# zulu_a7_6.net
KiCad netlist of a schematic drawn in Altium Designer
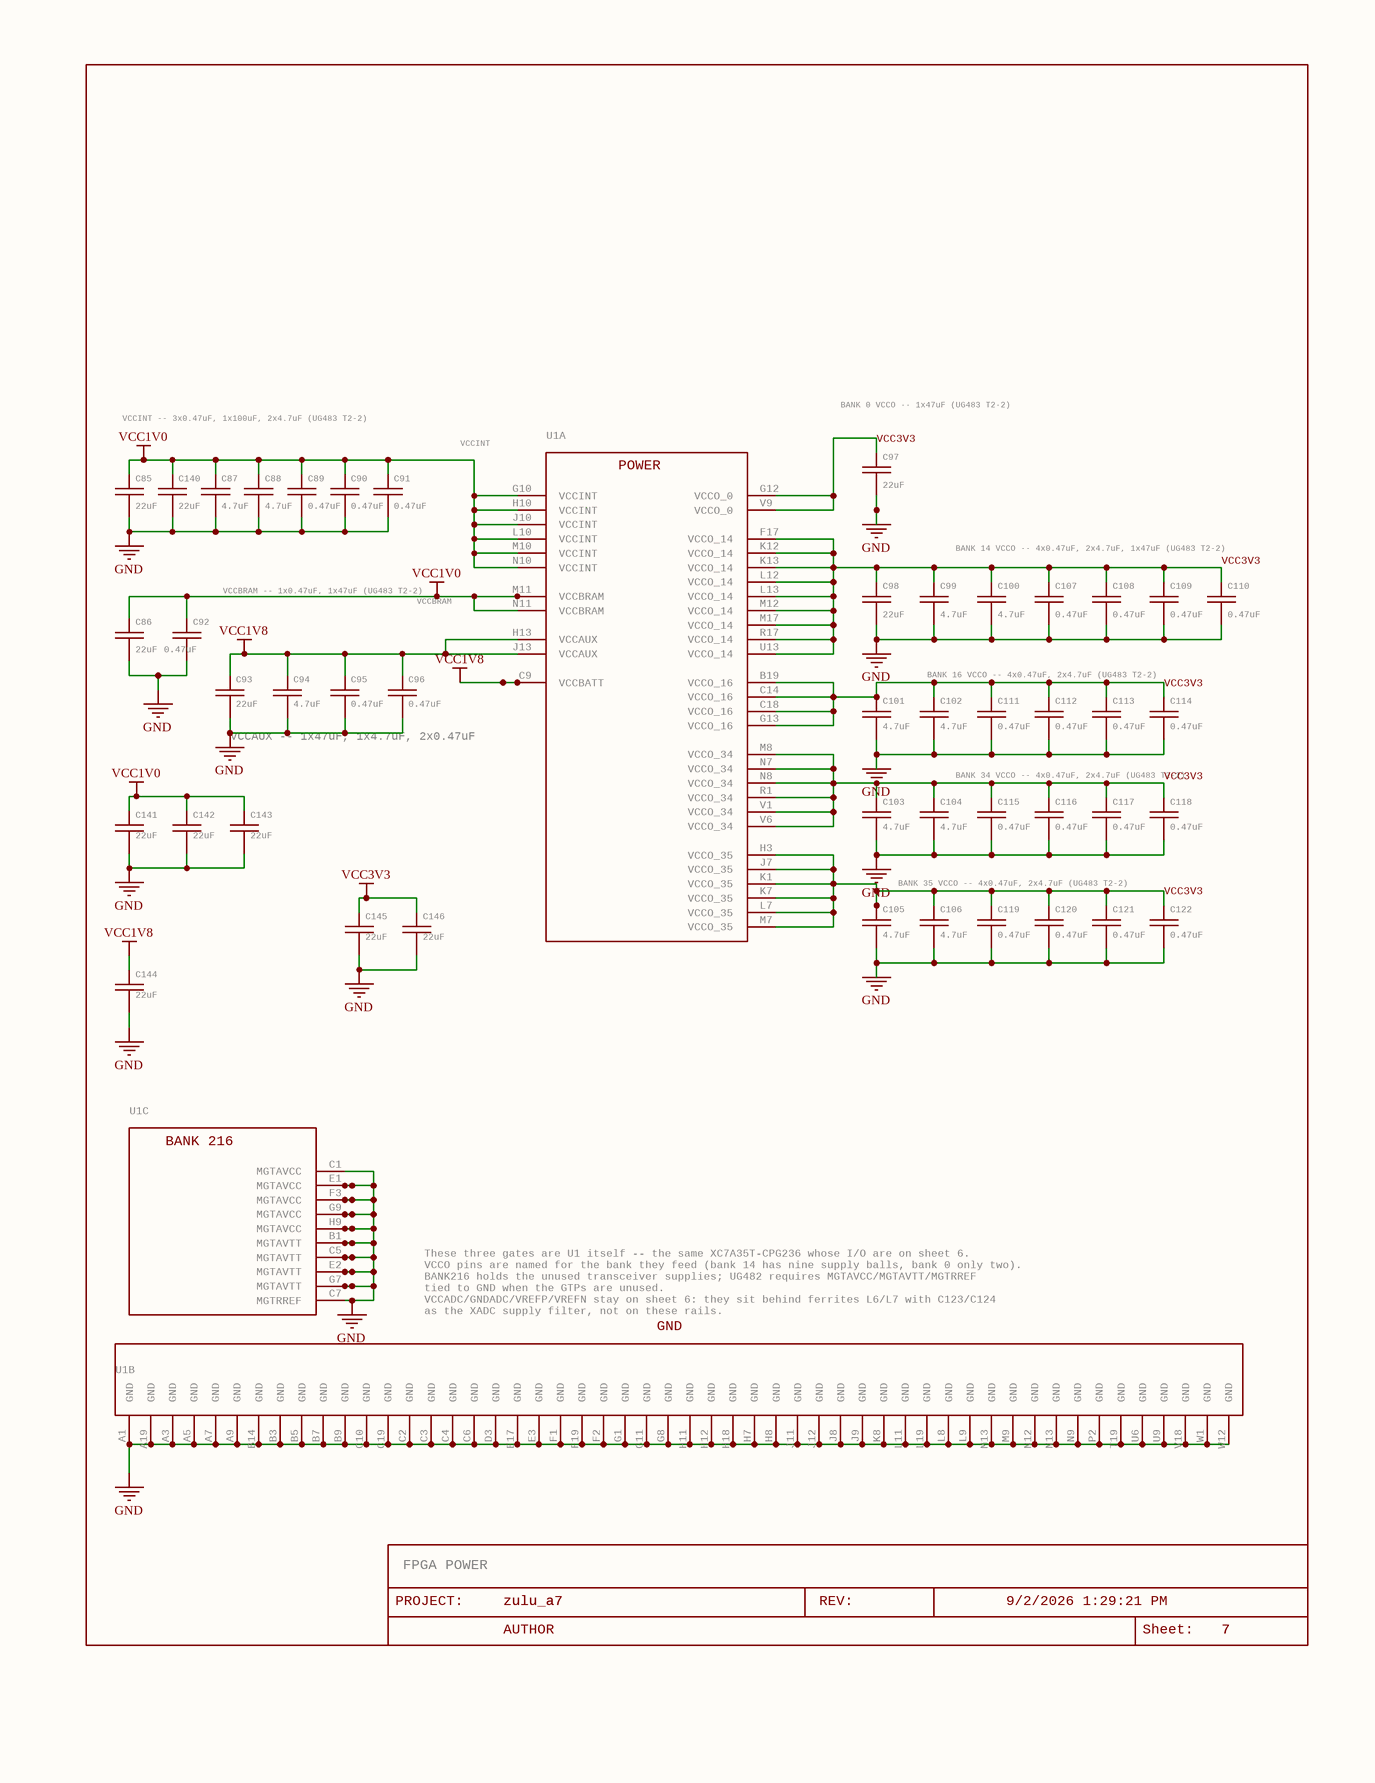
[diagram p0: zulu_a7_6.SchDoc]

(export (version "E")
  (design (tool "Eeschema 10.0.6"))
  (components
    (comp (ref "C85")
      (value "22uF")
      (footprint "C0805")
      (description "CAPACITOR, American symbol")
      (fields (field (name "MANF") "Murata"))
      (libsource (lib "rcl") (part "C-USC0805"))
    )
    (comp (ref "C86")
      (value "22uF")
      (footprint "C0805")
      (description "CAPACITOR, American symbol")
      (fields (field (name "MANF") "Murata"))
      (libsource (lib "rcl") (part "C-USC0805"))
    )
    (comp (ref "C87")
      (value "4.7uF")
      (footprint "C0603")
      (description "CAPACITOR, American symbol")
      (fields (field (name "MANF") "Murata"))
      (libsource (lib "rcl") (part "C-USC0603"))
    )
    (comp (ref "C88")
      (value "4.7uF")
      (footprint "C0603")
      (description "CAPACITOR, American symbol")
      (fields (field (name "MANF") "Murata"))
      (libsource (lib "rcl") (part "C-USC0603"))
    )
    (comp (ref "C89")
      (value "0.47uF")
      (footprint "C0201")
      (description "CAPACITOR, American symbol")
      (fields (field (name "MANF") "Murata"))
      (libsource (lib "rcl") (part "C-USC0201"))
    )
    (comp (ref "C90")
      (value "0.47uF")
      (footprint "C0201")
      (description "CAPACITOR, American symbol")
      (fields (field (name "MANF") "Murata"))
      (libsource (lib "rcl") (part "C-USC0201"))
    )
    (comp (ref "C91")
      (value "0.47uF")
      (footprint "C0201")
      (description "CAPACITOR, American symbol")
      (fields (field (name "MANF") "Murata"))
      (libsource (lib "rcl") (part "C-USC0201"))
    )
    (comp (ref "C92")
      (value "0.47uF")
      (footprint "C0201")
      (description "CAPACITOR, American symbol")
      (fields (field (name "MANF") "Murata"))
      (libsource (lib "rcl") (part "C-USC0201"))
    )
    (comp (ref "C93")
      (value "22uF")
      (footprint "C0805")
      (description "CAPACITOR, American symbol")
      (fields (field (name "MANF") "Murata"))
      (libsource (lib "rcl") (part "C-USC0805"))
    )
    (comp (ref "C94")
      (value "4.7uF")
      (footprint "C0603")
      (description "CAPACITOR, American symbol")
      (fields (field (name "MANF") "Murata"))
      (libsource (lib "rcl") (part "C-USC0603"))
    )
    (comp (ref "C95")
      (value "0.47uF")
      (footprint "C0201")
      (description "CAPACITOR, American symbol")
      (fields (field (name "MANF") "Murata"))
      (libsource (lib "rcl") (part "C-USC0201"))
    )
    (comp (ref "C96")
      (value "0.47uF")
      (footprint "C0201")
      (description "CAPACITOR, American symbol")
      (fields (field (name "MANF") "Murata"))
      (libsource (lib "rcl") (part "C-USC0201"))
    )
    (comp (ref "C97")
      (value "22uF")
      (footprint "C0805")
      (description "CAPACITOR, American symbol")
      (fields (field (name "MANF") "Murata"))
      (libsource (lib "rcl") (part "C-USC0805"))
    )
    (comp (ref "C98")
      (value "22uF")
      (footprint "C0805")
      (description "CAPACITOR, American symbol")
      (fields (field (name "MANF") "Murata"))
      (libsource (lib "rcl") (part "C-USC0805"))
    )
    (comp (ref "C99")
      (value "4.7uF")
      (footprint "C0603")
      (description "CAPACITOR, American symbol")
      (fields (field (name "MANF") "Murata"))
      (libsource (lib "rcl") (part "C-USC0603"))
    )
    (comp (ref "C100")
      (value "4.7uF")
      (footprint "C0603")
      (description "CAPACITOR, American symbol")
      (fields (field (name "MANF") "Murata"))
      (libsource (lib "rcl") (part "C-USC0603"))
    )
    (comp (ref "C101")
      (value "4.7uF")
      (footprint "C0603")
      (description "CAPACITOR, American symbol")
      (fields (field (name "MANF") "Murata"))
      (libsource (lib "rcl") (part "C-USC0603"))
    )
    (comp (ref "C102")
      (value "4.7uF")
      (footprint "C0603")
      (description "CAPACITOR, American symbol")
      (fields (field (name "MANF") "Murata"))
      (libsource (lib "rcl") (part "C-USC0603"))
    )
    (comp (ref "C103")
      (value "4.7uF")
      (footprint "C0603")
      (description "CAPACITOR, American symbol")
      (fields (field (name "MANF") "Murata"))
      (libsource (lib "rcl") (part "C-USC0603"))
    )
    (comp (ref "C104")
      (value "4.7uF")
      (footprint "C0603")
      (description "CAPACITOR, American symbol")
      (fields (field (name "MANF") "Murata"))
      (libsource (lib "rcl") (part "C-USC0603"))
    )
    (comp (ref "C105")
      (value "4.7uF")
      (footprint "C0603")
      (description "CAPACITOR, American symbol")
      (fields (field (name "MANF") "Murata"))
      (libsource (lib "rcl") (part "C-USC0603"))
    )
    (comp (ref "C106")
      (value "4.7uF")
      (footprint "C0603")
      (description "CAPACITOR, American symbol")
      (fields (field (name "MANF") "Murata"))
      (libsource (lib "rcl") (part "C-USC0603"))
    )
    (comp (ref "C107")
      (value "0.47uF")
      (footprint "C0201")
      (description "CAPACITOR, American symbol")
      (fields (field (name "MANF") "Murata"))
      (libsource (lib "rcl") (part "C-USC0201"))
    )
    (comp (ref "C108")
      (value "0.47uF")
      (footprint "C0201")
      (description "CAPACITOR, American symbol")
      (fields (field (name "MANF") "Murata"))
      (libsource (lib "rcl") (part "C-USC0201"))
    )
    (comp (ref "C109")
      (value "0.47uF")
      (footprint "C0201")
      (description "CAPACITOR, American symbol")
      (fields (field (name "MANF") "Murata"))
      (libsource (lib "rcl") (part "C-USC0201"))
    )
    (comp (ref "C110")
      (value "0.47uF")
      (footprint "C0201")
      (description "CAPACITOR, American symbol")
      (fields (field (name "MANF") "Murata"))
      (libsource (lib "rcl") (part "C-USC0201"))
    )
    (comp (ref "C111")
      (value "0.47uF")
      (footprint "C0201")
      (description "CAPACITOR, American symbol")
      (fields (field (name "MANF") "Murata"))
      (libsource (lib "rcl") (part "C-USC0201"))
    )
    (comp (ref "C112")
      (value "0.47uF")
      (footprint "C0201")
      (description "CAPACITOR, American symbol")
      (fields (field (name "MANF") "Murata"))
      (libsource (lib "rcl") (part "C-USC0201"))
    )
    (comp (ref "C113")
      (value "0.47uF")
      (footprint "C0201")
      (description "CAPACITOR, American symbol")
      (fields (field (name "MANF") "Murata"))
      (libsource (lib "rcl") (part "C-USC0201"))
    )
    (comp (ref "C114")
      (value "0.47uF")
      (footprint "C0201")
      (description "CAPACITOR, American symbol")
      (fields (field (name "MANF") "Murata"))
      (libsource (lib "rcl") (part "C-USC0201"))
    )
    (comp (ref "C115")
      (value "0.47uF")
      (footprint "C0201")
      (description "CAPACITOR, American symbol")
      (fields (field (name "MANF") "Murata"))
      (libsource (lib "rcl") (part "C-USC0201"))
    )
    (comp (ref "C116")
      (value "0.47uF")
      (footprint "C0201")
      (description "CAPACITOR, American symbol")
      (fields (field (name "MANF") "Murata"))
      (libsource (lib "rcl") (part "C-USC0201"))
    )
    (comp (ref "C117")
      (value "0.47uF")
      (footprint "C0201")
      (description "CAPACITOR, American symbol")
      (fields (field (name "MANF") "Murata"))
      (libsource (lib "rcl") (part "C-USC0201"))
    )
    (comp (ref "C118")
      (value "0.47uF")
      (footprint "C0201")
      (description "CAPACITOR, American symbol")
      (fields (field (name "MANF") "Murata"))
      (libsource (lib "rcl") (part "C-USC0201"))
    )
    (comp (ref "C119")
      (value "0.47uF")
      (footprint "C0201")
      (description "CAPACITOR, American symbol")
      (fields (field (name "MANF") "Murata"))
      (libsource (lib "rcl") (part "C-USC0201"))
    )
    (comp (ref "C120")
      (value "0.47uF")
      (footprint "C0201")
      (description "CAPACITOR, American symbol")
      (fields (field (name "MANF") "Murata"))
      (libsource (lib "rcl") (part "C-USC0201"))
    )
    (comp (ref "C121")
      (value "0.47uF")
      (footprint "C0201")
      (description "CAPACITOR, American symbol")
      (fields (field (name "MANF") "Murata"))
      (libsource (lib "rcl") (part "C-USC0201"))
    )
    (comp (ref "C122")
      (value "0.47uF")
      (footprint "C0201")
      (description "CAPACITOR, American symbol")
      (fields (field (name "MANF") "Murata"))
      (libsource (lib "rcl") (part "C-USC0201"))
    )
    (comp (ref "C140")
      (value "22uF")
      (footprint "C0805")
      (description "CAPACITOR, American symbol")
      (fields (field (name "MANF") "Murata"))
      (libsource (lib "rcl") (part "C-USC0805"))
    )
    (comp (ref "C141")
      (value "22uF")
      (footprint "C0805")
      (description "CAPACITOR, American symbol")
      (fields (field (name "MANF") "Murata"))
      (libsource (lib "rcl") (part "C-USC0805"))
    )
    (comp (ref "C142")
      (value "22uF")
      (footprint "C0805")
      (description "CAPACITOR, American symbol")
      (fields (field (name "MANF") "Murata"))
      (libsource (lib "rcl") (part "C-USC0805"))
    )
    (comp (ref "C143")
      (value "22uF")
      (footprint "C0805")
      (description "CAPACITOR, American symbol")
      (fields (field (name "MANF") "Murata"))
      (libsource (lib "rcl") (part "C-USC0805"))
    )
    (comp (ref "C144")
      (value "22uF")
      (footprint "C0805")
      (description "CAPACITOR, American symbol")
      (fields (field (name "MANF") "Murata"))
      (libsource (lib "") (part "C-USC0805_1"))
    )
    (comp (ref "C145")
      (value "22uF")
      (footprint "C0805")
      (description "CAPACITOR, American symbol")
      (fields (field (name "MANF") "Murata"))
      (libsource (lib "") (part "C-USC0805_2"))
    )
    (comp (ref "C146")
      (value "22uF")
      (footprint "C0805")
      (description "CAPACITOR, American symbol")
      (fields (field (name "MANF") "Murata"))
      (libsource (lib "") (part "C-USC0805_2"))
    )
    (comp (ref "FRAME6")
      (value "DOCFIELD")
      (description "DOCUMENT FIELD")
      (fields
        (field (name "LAST_DATE_TIME") "9/2/2026 1:29:21 PM")
        (field (name "SHEET") "Sheet:")
        (field (name "SHEET_1") "7")
        (field (name "REV") "REV:")
        (field (name "PROJECT") "PROJECT:")
        (field (name "DRAWING_NAME") "zulu_a7")
        (field (name "AUTHOR") "AUTHOR")
        (field (name "DRAWING_NAME_1") "zulu_a7")
        (field (name "SHEET_2") "7")
        (field (name "LIBRARYNAME") "ctambe")
      )
      (libsource (lib "ctambe") (part "DOCFIELD"))
    )
    (comp (ref "U1")
      (value "XC7A35T-1CPG236C")
      (footprint "XC7A35T-CPG236")
      (fields
        (field (name "GND") "GND")
        (field (name "MANF") "AMD/Xilinx")
        (field (name "BANK216") "BANK 216")
        (field (name "POWER") "POWER")
        (field (name "LIBRARYNAME") "ctambe")
      )
      (libsource (lib "ctambe") (part "XC7A35T-CPG236-1CPG236C"))
    )
  )
  (nets
    (net (code "1") (name "GND") (class "Default")
      (node (ref "C100") (pin "2") (pinfunction "2_2") (pintype "passive"))
      (node (ref "C101") (pin "2") (pinfunction "2_2") (pintype "passive"))
      (node (ref "C102") (pin "2") (pinfunction "2_2") (pintype "passive"))
      (node (ref "C103") (pin "2") (pinfunction "2_2") (pintype "passive"))
      (node (ref "C104") (pin "2") (pinfunction "2_2") (pintype "passive"))
      (node (ref "C105") (pin "2") (pinfunction "2_2") (pintype "passive"))
      (node (ref "C106") (pin "2") (pinfunction "2_2") (pintype "passive"))
      (node (ref "C107") (pin "2") (pinfunction "2_2") (pintype "passive"))
      (node (ref "C108") (pin "2") (pinfunction "2_2") (pintype "passive"))
      (node (ref "C109") (pin "2") (pinfunction "2_2") (pintype "passive"))
      (node (ref "C110") (pin "2") (pinfunction "2_2") (pintype "passive"))
      (node (ref "C111") (pin "2") (pinfunction "2_2") (pintype "passive"))
      (node (ref "C112") (pin "2") (pinfunction "2_2") (pintype "passive"))
      (node (ref "C113") (pin "2") (pinfunction "2_2") (pintype "passive"))
      (node (ref "C114") (pin "2") (pinfunction "2_2") (pintype "passive"))
      (node (ref "C115") (pin "2") (pinfunction "2_2") (pintype "passive"))
      (node (ref "C116") (pin "2") (pinfunction "2_2") (pintype "passive"))
      (node (ref "C117") (pin "2") (pinfunction "2_2") (pintype "passive"))
      (node (ref "C118") (pin "2") (pinfunction "2_2") (pintype "passive"))
      (node (ref "C119") (pin "2") (pinfunction "2_2") (pintype "passive"))
      (node (ref "C120") (pin "2") (pinfunction "2_2") (pintype "passive"))
      (node (ref "C121") (pin "2") (pinfunction "2_2") (pintype "passive"))
      (node (ref "C122") (pin "2") (pinfunction "2_2") (pintype "passive"))
      (node (ref "C140") (pin "2") (pinfunction "2_2") (pintype "passive"))
      (node (ref "C141") (pin "2") (pinfunction "2_2") (pintype "passive"))
      (node (ref "C142") (pin "2") (pinfunction "2_2") (pintype "passive"))
      (node (ref "C143") (pin "2") (pinfunction "2_2") (pintype "passive"))
      (node (ref "C144") (pin "2") (pinfunction "2_2") (pintype "passive"))
      (node (ref "C145") (pin "2") (pinfunction "2_2") (pintype "passive"))
      (node (ref "C146") (pin "2") (pinfunction "2_2") (pintype "passive"))
      (node (ref "C85") (pin "2") (pinfunction "2_2") (pintype "passive"))
      (node (ref "C86") (pin "2") (pinfunction "2_2") (pintype "passive"))
      (node (ref "C87") (pin "2") (pinfunction "2_2") (pintype "passive"))
      (node (ref "C88") (pin "2") (pinfunction "2_2") (pintype "passive"))
      (node (ref "C89") (pin "2") (pinfunction "2_2") (pintype "passive"))
      (node (ref "C90") (pin "2") (pinfunction "2_2") (pintype "passive"))
      (node (ref "C91") (pin "2") (pinfunction "2_2") (pintype "passive"))
      (node (ref "C92") (pin "2") (pinfunction "2_2") (pintype "passive"))
      (node (ref "C93") (pin "2") (pinfunction "2_2") (pintype "passive"))
      (node (ref "C94") (pin "2") (pinfunction "2_2") (pintype "passive"))
      (node (ref "C95") (pin "2") (pinfunction "2_2") (pintype "passive"))
      (node (ref "C96") (pin "2") (pinfunction "2_2") (pintype "passive"))
      (node (ref "C97") (pin "2") (pinfunction "2_2") (pintype "passive"))
      (node (ref "C98") (pin "2") (pinfunction "2_2") (pintype "passive"))
      (node (ref "C99") (pin "2") (pinfunction "2_2") (pintype "passive"))
      (node (ref "U1") (pin "A1") (pinfunction "GND_A1") (pintype "power_in"))
      (node (ref "U1") (pin "A19") (pinfunction "GND_A19") (pintype "power_in"))
      (node (ref "U1") (pin "A3") (pinfunction "GND_A3") (pintype "power_in"))
      (node (ref "U1") (pin "A5") (pinfunction "GND_A5") (pintype "power_in"))
      (node (ref "U1") (pin "A7") (pinfunction "GND_A7") (pintype "power_in"))
      (node (ref "U1") (pin "A9") (pinfunction "GND_A9") (pintype "power_in"))
      (node (ref "U1") (pin "B1") (pinfunction "MGTAVTT_B1") (pintype "power_in"))
      (node (ref "U1") (pin "B14") (pinfunction "GND_B14") (pintype "power_in"))
      (node (ref "U1") (pin "B3") (pinfunction "GND_B3") (pintype "power_in"))
      (node (ref "U1") (pin "B5") (pinfunction "GND_B5") (pintype "power_in"))
      (node (ref "U1") (pin "B7") (pinfunction "GND_B7") (pintype "power_in"))
      (node (ref "U1") (pin "B9") (pinfunction "GND_B9") (pintype "power_in"))
      (node (ref "U1") (pin "C1") (pinfunction "MGTAVCC_C1") (pintype "power_in"))
      (node (ref "U1") (pin "C10") (pinfunction "GND_C10") (pintype "power_in"))
      (node (ref "U1") (pin "C19") (pinfunction "GND_C19") (pintype "power_in"))
      (node (ref "U1") (pin "C2") (pinfunction "GND_C2") (pintype "power_in"))
      (node (ref "U1") (pin "C3") (pinfunction "GND_C3") (pintype "power_in"))
      (node (ref "U1") (pin "C4") (pinfunction "GND_C4") (pintype "power_in"))
      (node (ref "U1") (pin "C5") (pinfunction "MGTAVTT_C5") (pintype "power_in"))
      (node (ref "U1") (pin "C6") (pinfunction "GND_C6") (pintype "power_in"))
      (node (ref "U1") (pin "C7") (pinfunction "MGTRREF_C7") (pintype "power_in"))
      (node (ref "U1") (pin "D3") (pinfunction "GND_D3") (pintype "power_in"))
      (node (ref "U1") (pin "E1") (pinfunction "MGTAVCC_E1") (pintype "power_in"))
      (node (ref "U1") (pin "E17") (pinfunction "GND_E17") (pintype "power_in"))
      (node (ref "U1") (pin "E2") (pinfunction "MGTAVTT_E2") (pintype "power_in"))
      (node (ref "U1") (pin "E3") (pinfunction "GND_E3") (pintype "power_in"))
      (node (ref "U1") (pin "F1") (pinfunction "GND_F1") (pintype "power_in"))
      (node (ref "U1") (pin "F19") (pinfunction "GND_F19") (pintype "power_in"))
      (node (ref "U1") (pin "F2") (pinfunction "GND_F2") (pintype "power_in"))
      (node (ref "U1") (pin "F3") (pinfunction "MGTAVCC_F3") (pintype "power_in"))
      (node (ref "U1") (pin "G1") (pinfunction "GND_G1") (pintype "power_in"))
      (node (ref "U1") (pin "G11") (pinfunction "GND_G11") (pintype "power_in"))
      (node (ref "U1") (pin "G7") (pinfunction "MGTAVTT_G7") (pintype "power_in"))
      (node (ref "U1") (pin "G8") (pinfunction "GND_G8") (pintype "power_in"))
      (node (ref "U1") (pin "G9") (pinfunction "MGTAVCC_G9") (pintype "power_in"))
      (node (ref "U1") (pin "H11") (pinfunction "GND_H11") (pintype "power_in"))
      (node (ref "U1") (pin "H12") (pinfunction "GND_H12") (pintype "power_in"))
      (node (ref "U1") (pin "H18") (pinfunction "GND_H18") (pintype "power_in"))
      (node (ref "U1") (pin "H7") (pinfunction "GND_H7") (pintype "power_in"))
      (node (ref "U1") (pin "H8") (pinfunction "GND_H8") (pintype "power_in"))
      (node (ref "U1") (pin "H9") (pinfunction "MGTAVCC_H9") (pintype "power_in"))
      (node (ref "U1") (pin "J11") (pinfunction "GND_J11") (pintype "power_in"))
      (node (ref "U1") (pin "J12") (pinfunction "GND_J12") (pintype "power_in"))
      (node (ref "U1") (pin "J8") (pinfunction "GND_J8") (pintype "power_in"))
      (node (ref "U1") (pin "J9") (pinfunction "GND_J9") (pintype "power_in"))
      (node (ref "U1") (pin "K8") (pinfunction "GND_K8") (pintype "power_in"))
      (node (ref "U1") (pin "L11") (pinfunction "GND_L11") (pintype "power_in"))
      (node (ref "U1") (pin "L19") (pinfunction "GND_L19") (pintype "power_in"))
      (node (ref "U1") (pin "L8") (pinfunction "GND_L8") (pintype "power_in"))
      (node (ref "U1") (pin "L9") (pinfunction "GND_L9") (pintype "power_in"))
      (node (ref "U1") (pin "M13") (pinfunction "GND_M13") (pintype "power_in"))
      (node (ref "U1") (pin "M9") (pinfunction "GND_M9") (pintype "power_in"))
      (node (ref "U1") (pin "N12") (pinfunction "GND_N12") (pintype "power_in"))
      (node (ref "U1") (pin "N13") (pinfunction "GND_N13") (pintype "power_in"))
      (node (ref "U1") (pin "N9") (pinfunction "GND_N9") (pintype "power_in"))
      (node (ref "U1") (pin "P2") (pinfunction "GND_P2") (pintype "power_in"))
      (node (ref "U1") (pin "T19") (pinfunction "GND_T19") (pintype "power_in"))
      (node (ref "U1") (pin "U6") (pinfunction "GND_U6") (pintype "power_in"))
      (node (ref "U1") (pin "U9") (pinfunction "GND_U9") (pintype "power_in"))
      (node (ref "U1") (pin "V18") (pinfunction "GND_V18") (pintype "power_in"))
      (node (ref "U1") (pin "W1") (pinfunction "GND_W1") (pintype "power_in"))
      (node (ref "U1") (pin "W12") (pinfunction "GND_W12") (pintype "power_in"))
    )
    (net (code "2") (name "VCC1V0") (class "Default")
      (node (ref "C140") (pin "1") (pinfunction "1_1") (pintype "passive"))
      (node (ref "C141") (pin "1") (pinfunction "1_1") (pintype "passive"))
      (node (ref "C142") (pin "1") (pinfunction "1_1") (pintype "passive"))
      (node (ref "C143") (pin "1") (pinfunction "1_1") (pintype "passive"))
      (node (ref "C85") (pin "1") (pinfunction "1_1") (pintype "passive"))
      (node (ref "C86") (pin "1") (pinfunction "1_1") (pintype "passive"))
      (node (ref "C87") (pin "1") (pinfunction "1_1") (pintype "passive"))
      (node (ref "C88") (pin "1") (pinfunction "1_1") (pintype "passive"))
      (node (ref "C89") (pin "1") (pinfunction "1_1") (pintype "passive"))
      (node (ref "C90") (pin "1") (pinfunction "1_1") (pintype "passive"))
      (node (ref "C91") (pin "1") (pinfunction "1_1") (pintype "passive"))
      (node (ref "C92") (pin "1") (pinfunction "1_1") (pintype "passive"))
      (node (ref "U1") (pin "G10") (pinfunction "VCCINT_G10") (pintype "power_in"))
      (node (ref "U1") (pin "H10") (pinfunction "VCCINT_H10") (pintype "power_in"))
      (node (ref "U1") (pin "J10") (pinfunction "VCCINT_J10") (pintype "power_in"))
      (node (ref "U1") (pin "L10") (pinfunction "VCCINT_L10") (pintype "power_in"))
      (node (ref "U1") (pin "M10") (pinfunction "VCCINT_M10") (pintype "power_in"))
      (node (ref "U1") (pin "M11") (pinfunction "VCCBRAM_M11") (pintype "power_in"))
      (node (ref "U1") (pin "N10") (pinfunction "VCCINT_N10") (pintype "power_in"))
      (node (ref "U1") (pin "N11") (pinfunction "VCCBRAM_N11") (pintype "power_in"))
    )
    (net (code "3") (name "VCC1V8") (class "Default")
      (node (ref "C144") (pin "1") (pinfunction "1_1") (pintype "passive"))
      (node (ref "C93") (pin "1") (pinfunction "1_1") (pintype "passive"))
      (node (ref "C94") (pin "1") (pinfunction "1_1") (pintype "passive"))
      (node (ref "C95") (pin "1") (pinfunction "1_1") (pintype "passive"))
      (node (ref "C96") (pin "1") (pinfunction "1_1") (pintype "passive"))
      (node (ref "U1") (pin "C9") (pinfunction "VCCBATT_C9") (pintype "power_in"))
      (node (ref "U1") (pin "H13") (pinfunction "VCCAUX_H13") (pintype "power_in"))
      (node (ref "U1") (pin "J13") (pinfunction "VCCAUX_J13") (pintype "power_in"))
    )
    (net (code "4") (name "VCC3V3") (class "Default")
      (node (ref "C100") (pin "1") (pinfunction "1_1") (pintype "passive"))
      (node (ref "C101") (pin "1") (pinfunction "1_1") (pintype "passive"))
      (node (ref "C102") (pin "1") (pinfunction "1_1") (pintype "passive"))
      (node (ref "C103") (pin "1") (pinfunction "1_1") (pintype "passive"))
      (node (ref "C104") (pin "1") (pinfunction "1_1") (pintype "passive"))
      (node (ref "C105") (pin "1") (pinfunction "1_1") (pintype "passive"))
      (node (ref "C106") (pin "1") (pinfunction "1_1") (pintype "passive"))
      (node (ref "C107") (pin "1") (pinfunction "1_1") (pintype "passive"))
      (node (ref "C108") (pin "1") (pinfunction "1_1") (pintype "passive"))
      (node (ref "C109") (pin "1") (pinfunction "1_1") (pintype "passive"))
      (node (ref "C110") (pin "1") (pinfunction "1_1") (pintype "passive"))
      (node (ref "C111") (pin "1") (pinfunction "1_1") (pintype "passive"))
      (node (ref "C112") (pin "1") (pinfunction "1_1") (pintype "passive"))
      (node (ref "C113") (pin "1") (pinfunction "1_1") (pintype "passive"))
      (node (ref "C114") (pin "1") (pinfunction "1_1") (pintype "passive"))
      (node (ref "C115") (pin "1") (pinfunction "1_1") (pintype "passive"))
      (node (ref "C116") (pin "1") (pinfunction "1_1") (pintype "passive"))
      (node (ref "C117") (pin "1") (pinfunction "1_1") (pintype "passive"))
      (node (ref "C118") (pin "1") (pinfunction "1_1") (pintype "passive"))
      (node (ref "C119") (pin "1") (pinfunction "1_1") (pintype "passive"))
      (node (ref "C120") (pin "1") (pinfunction "1_1") (pintype "passive"))
      (node (ref "C121") (pin "1") (pinfunction "1_1") (pintype "passive"))
      (node (ref "C122") (pin "1") (pinfunction "1_1") (pintype "passive"))
      (node (ref "C145") (pin "1") (pinfunction "1_1") (pintype "passive"))
      (node (ref "C146") (pin "1") (pinfunction "1_1") (pintype "passive"))
      (node (ref "C97") (pin "1") (pinfunction "1_1") (pintype "passive"))
      (node (ref "C98") (pin "1") (pinfunction "1_1") (pintype "passive"))
      (node (ref "C99") (pin "1") (pinfunction "1_1") (pintype "passive"))
      (node (ref "U1") (pin "B19") (pinfunction "VCCO_16_B19") (pintype "power_in"))
      (node (ref "U1") (pin "C14") (pinfunction "VCCO_16_C14") (pintype "power_in"))
      (node (ref "U1") (pin "C18") (pinfunction "VCCO_16_C18") (pintype "power_in"))
      (node (ref "U1") (pin "F17") (pinfunction "VCCO_14_F17") (pintype "power_in"))
      (node (ref "U1") (pin "G12") (pinfunction "VCCO_0_G12") (pintype "power_in"))
      (node (ref "U1") (pin "G13") (pinfunction "VCCO_16_G13") (pintype "power_in"))
      (node (ref "U1") (pin "H3") (pinfunction "VCCO_35_H3") (pintype "power_in"))
      (node (ref "U1") (pin "J7") (pinfunction "VCCO_35_J7") (pintype "power_in"))
      (node (ref "U1") (pin "K1") (pinfunction "VCCO_35_K1") (pintype "power_in"))
      (node (ref "U1") (pin "K12") (pinfunction "VCCO_14_K12") (pintype "power_in"))
      (node (ref "U1") (pin "K13") (pinfunction "VCCO_14_K13") (pintype "power_in"))
      (node (ref "U1") (pin "K7") (pinfunction "VCCO_35_K7") (pintype "power_in"))
      (node (ref "U1") (pin "L12") (pinfunction "VCCO_14_L12") (pintype "power_in"))
      (node (ref "U1") (pin "L13") (pinfunction "VCCO_14_L13") (pintype "power_in"))
      (node (ref "U1") (pin "L7") (pinfunction "VCCO_35_L7") (pintype "power_in"))
      (node (ref "U1") (pin "M12") (pinfunction "VCCO_14_M12") (pintype "power_in"))
      (node (ref "U1") (pin "M17") (pinfunction "VCCO_14_M17") (pintype "power_in"))
      (node (ref "U1") (pin "M7") (pinfunction "VCCO_35_M7") (pintype "power_in"))
      (node (ref "U1") (pin "M8") (pinfunction "VCCO_34_M8") (pintype "power_in"))
      (node (ref "U1") (pin "N7") (pinfunction "VCCO_34_N7") (pintype "power_in"))
      (node (ref "U1") (pin "N8") (pinfunction "VCCO_34_N8") (pintype "power_in"))
      (node (ref "U1") (pin "R1") (pinfunction "VCCO_34_R1") (pintype "power_in"))
      (node (ref "U1") (pin "R17") (pinfunction "VCCO_14_R17") (pintype "power_in"))
      (node (ref "U1") (pin "U13") (pinfunction "VCCO_14_U13") (pintype "power_in"))
      (node (ref "U1") (pin "V1") (pinfunction "VCCO_34_V1") (pintype "power_in"))
      (node (ref "U1") (pin "V6") (pinfunction "VCCO_34_V6") (pintype "power_in"))
      (node (ref "U1") (pin "V9") (pinfunction "VCCO_0_V9") (pintype "power_in"))
    )
  )
)
